# H04.net
KiCad netlist of a schematic drawn in EAGLE
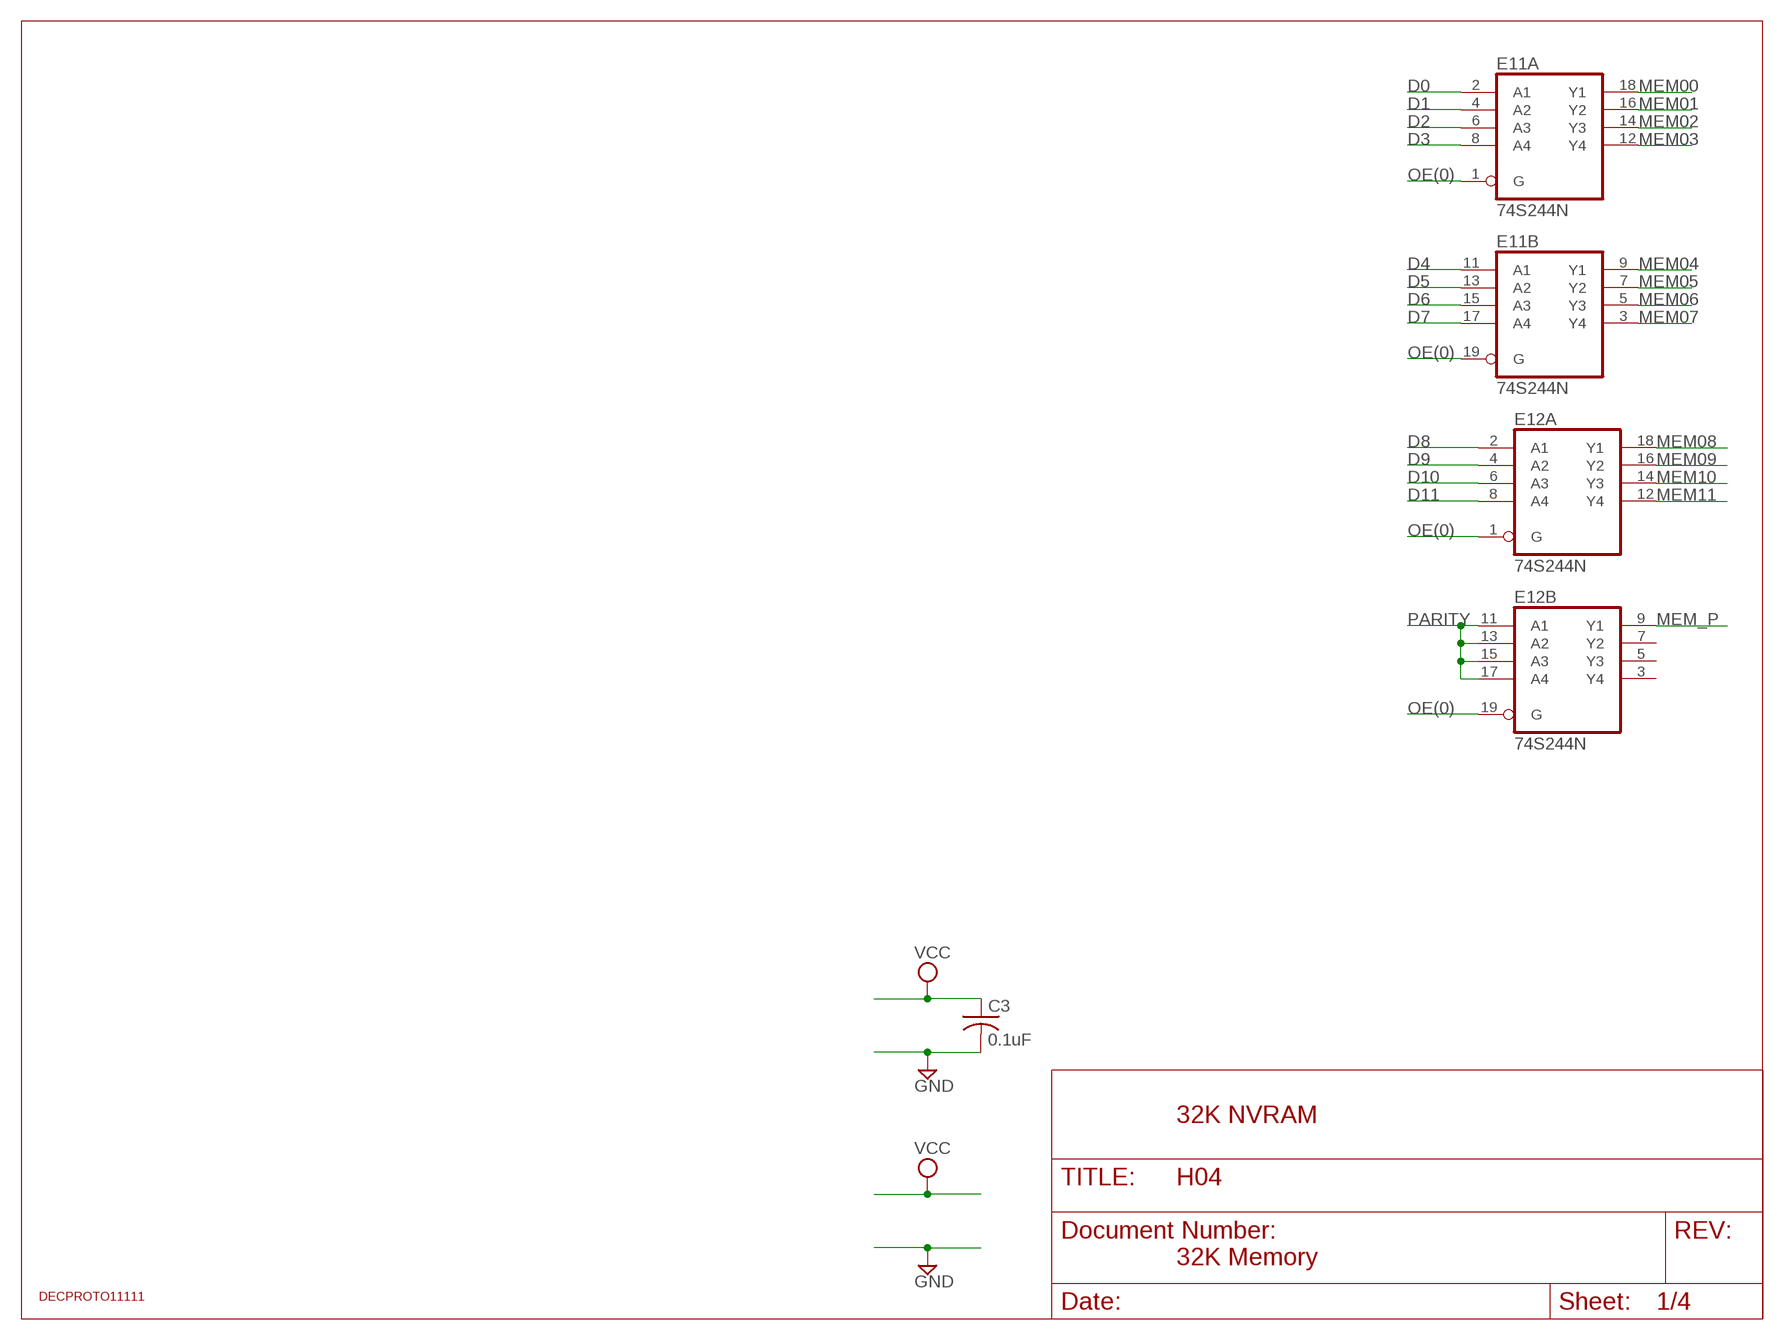
[diagram p0: schematic, sheet 1]
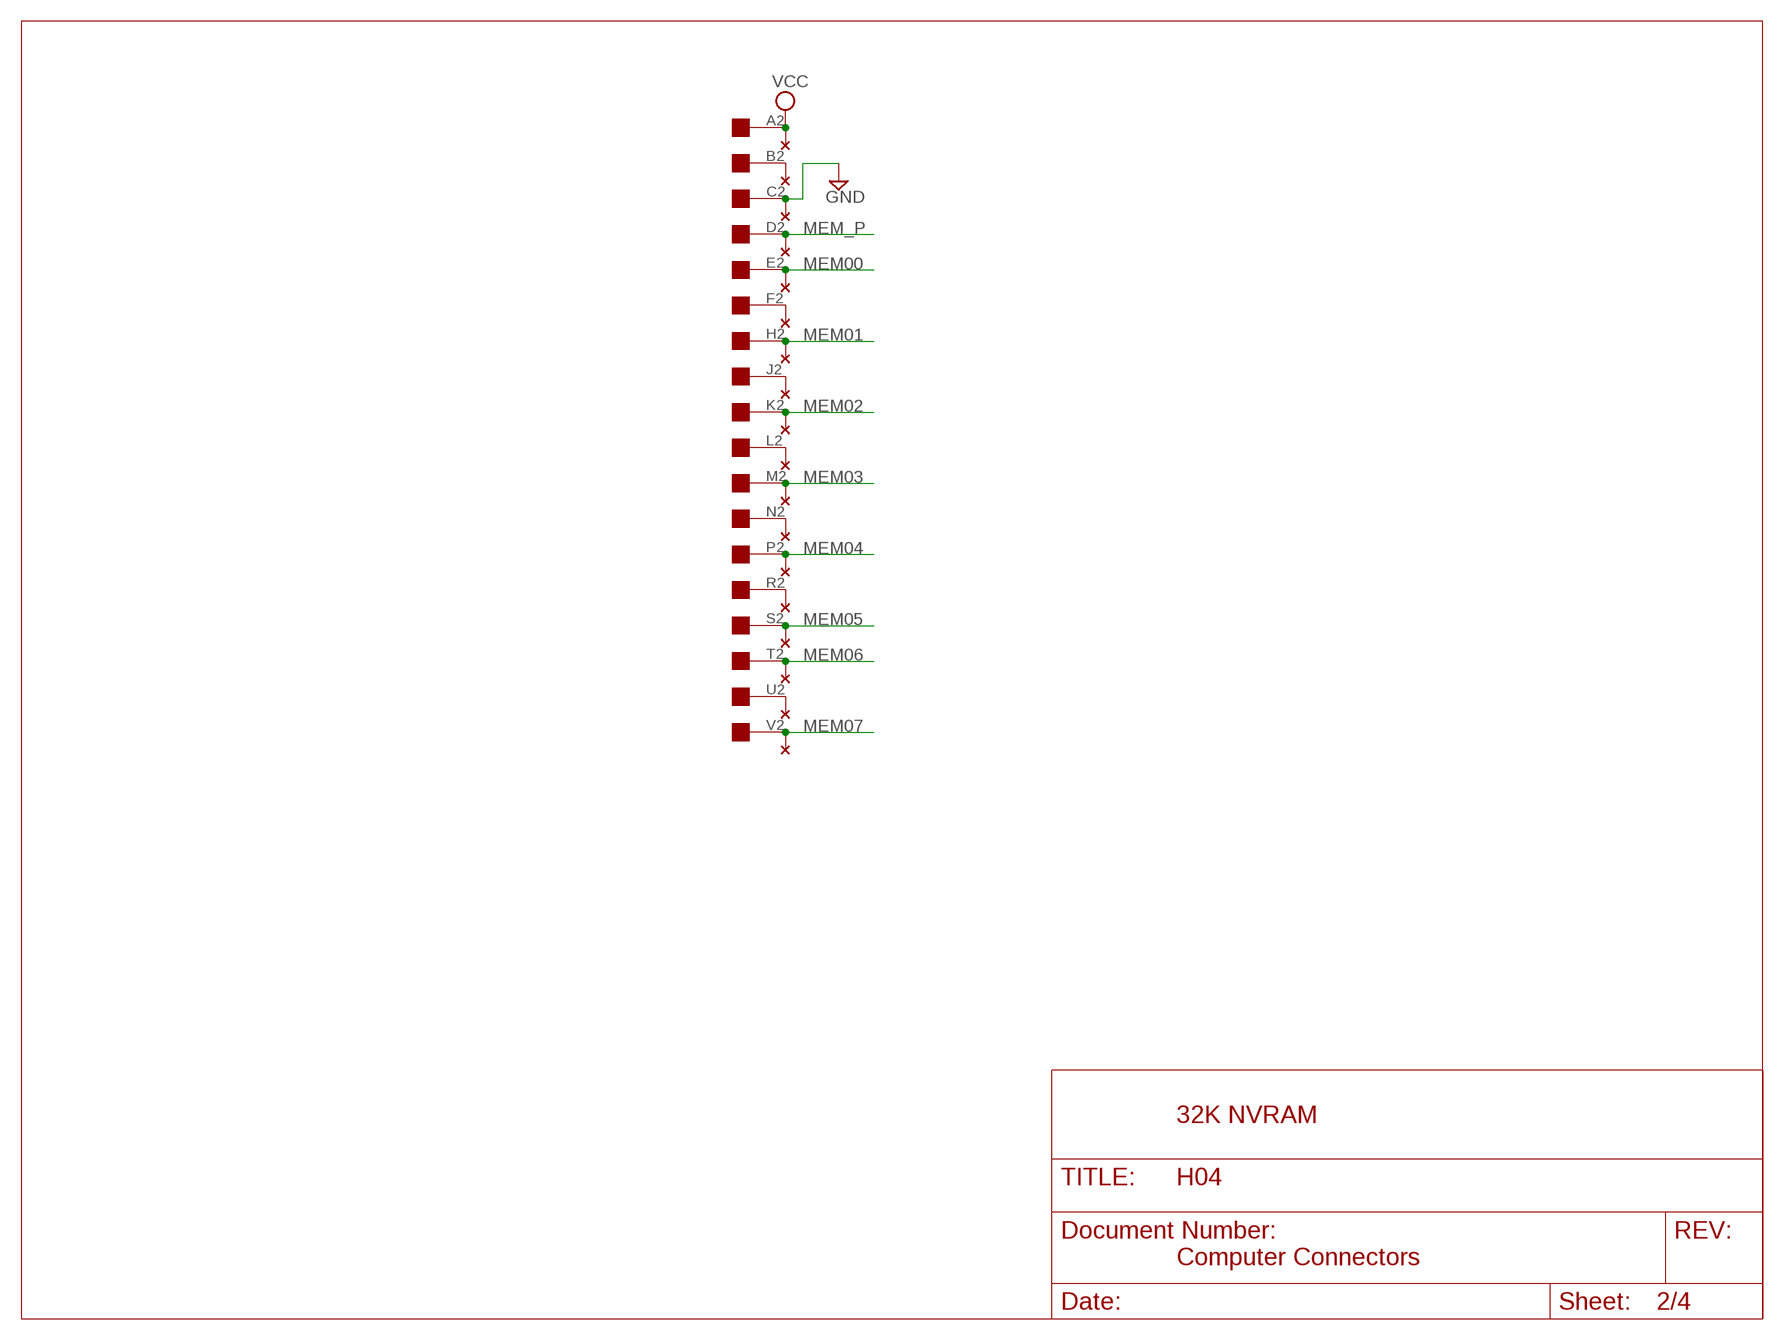
[diagram p1: schematic, sheet 2]
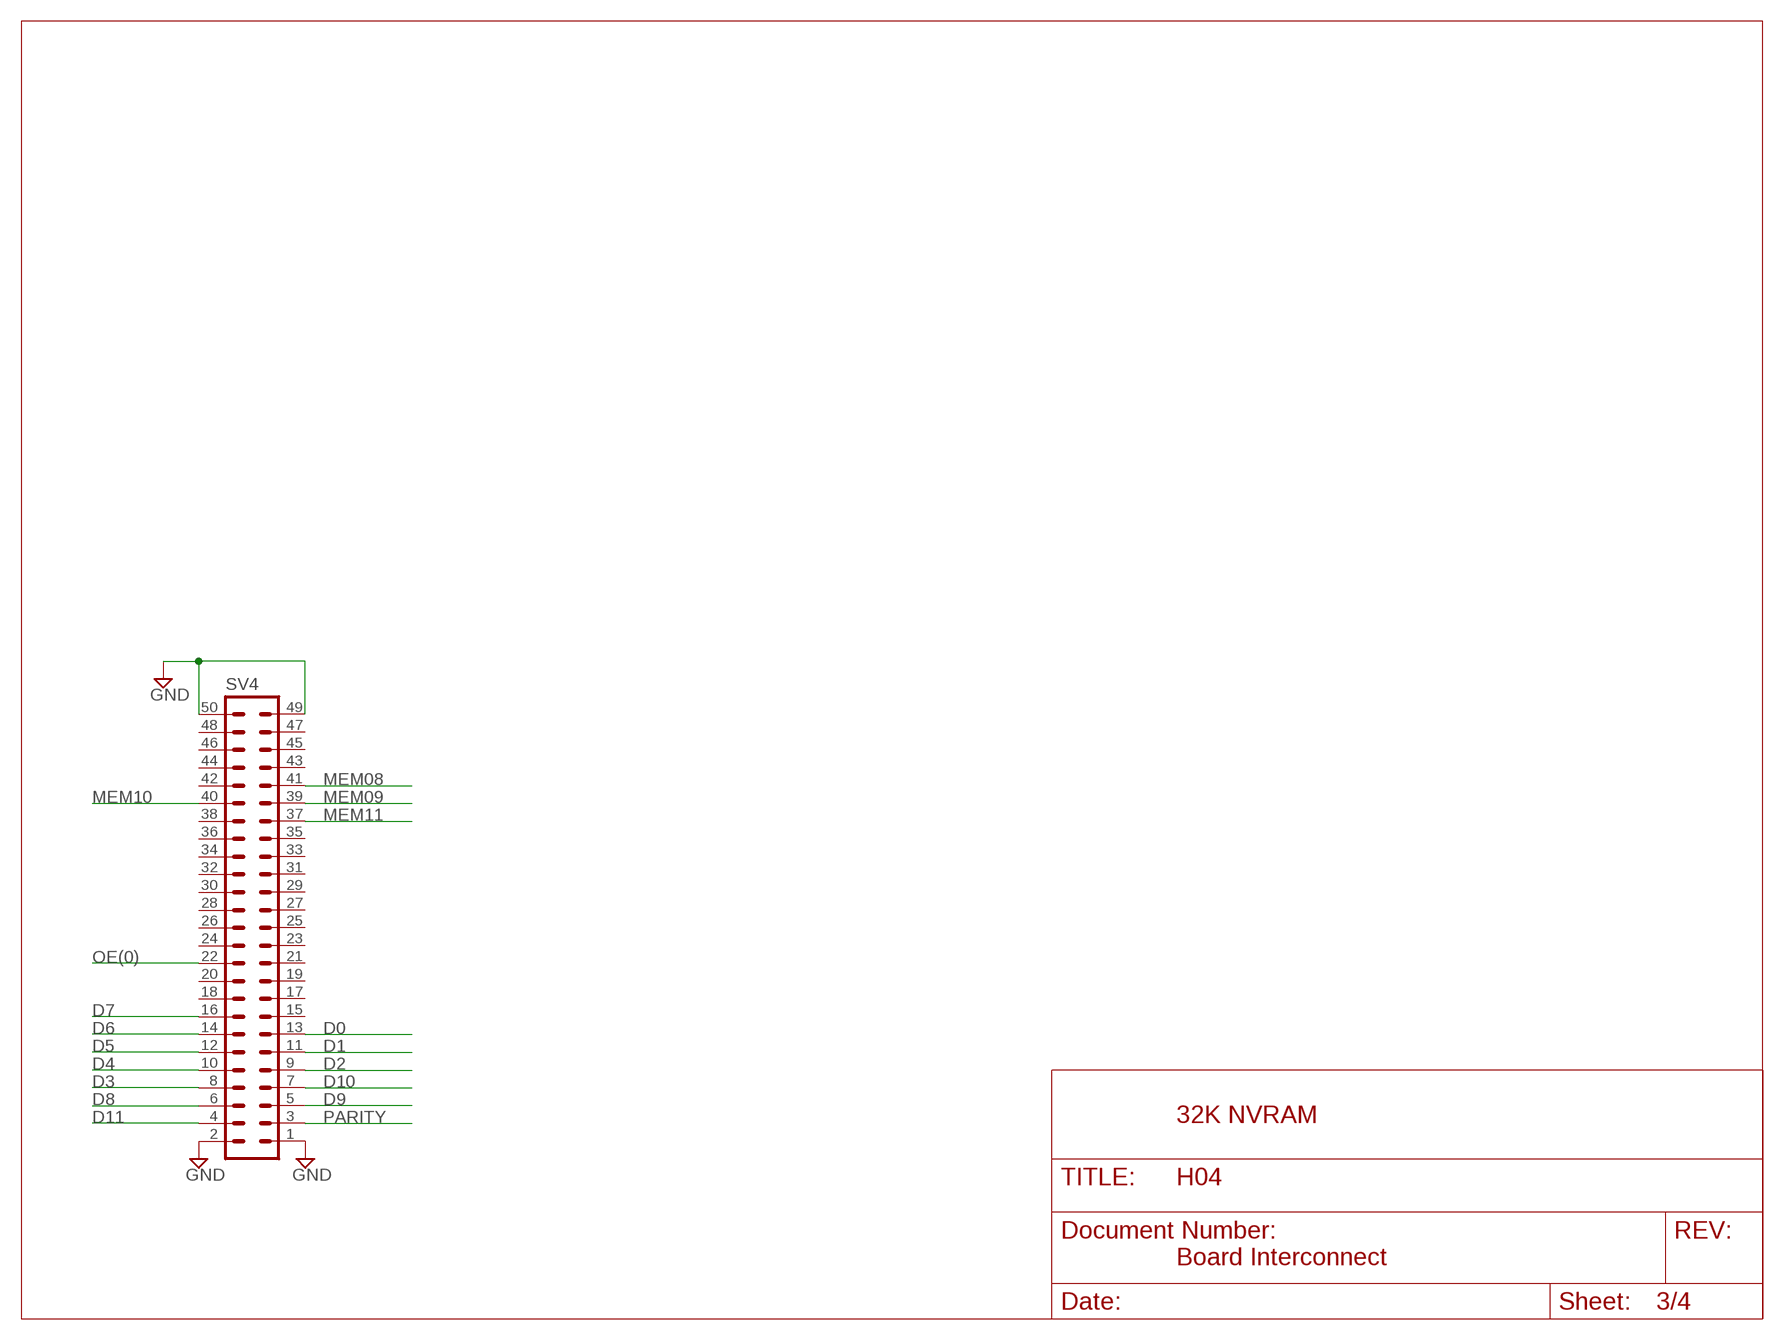
[diagram p2: schematic, sheet 3]
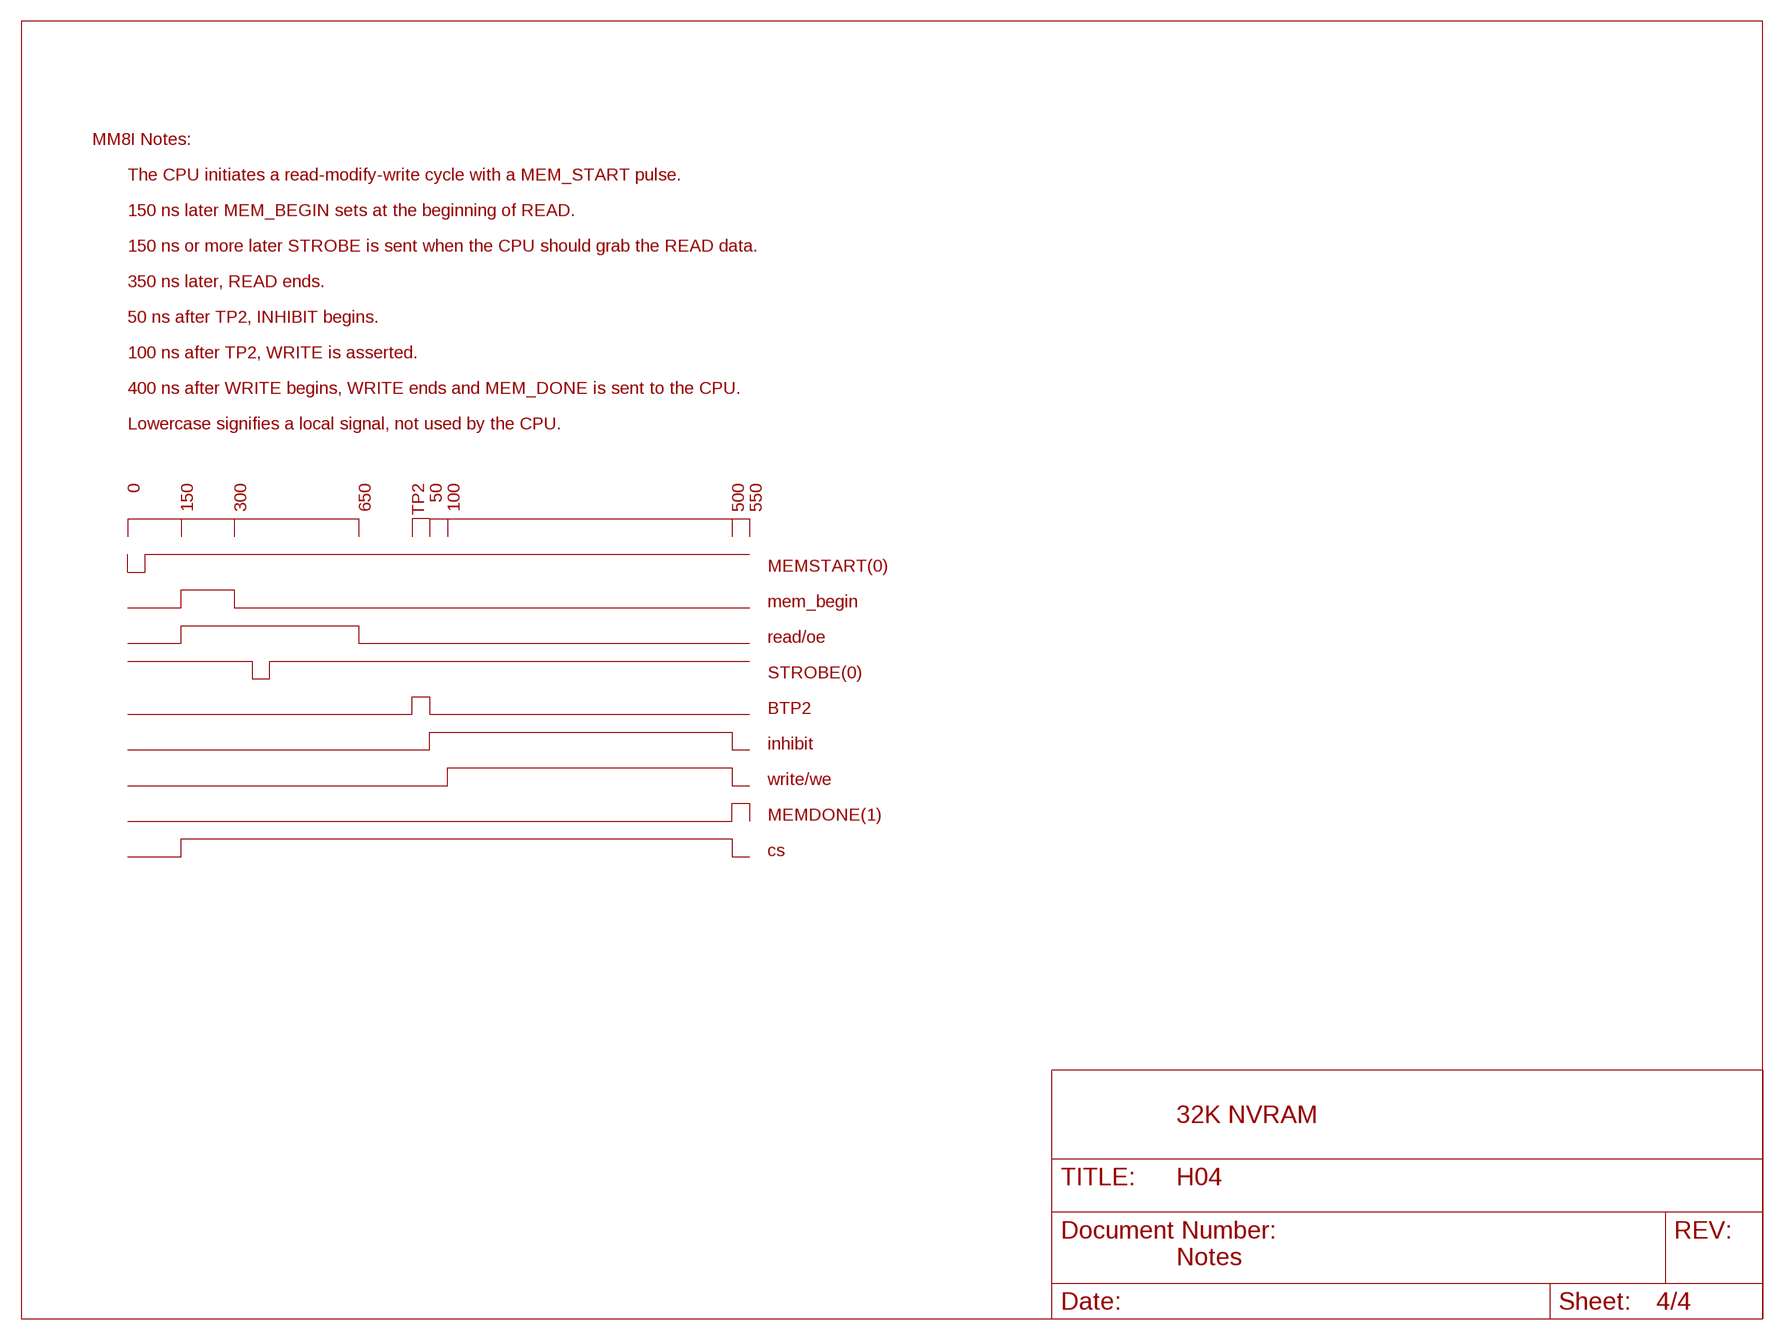
[diagram p3: schematic, sheet 4]

(export (version "E")
  (design (tool "Eeschema 10.0.6"))
  (components
    (comp (ref "SV4")
      (value "ML50L")
      (footprint "eagle-import:ML50L")
      (libsource (lib "eagle-import") (part "ML50L"))
    )
    (comp (ref "C3")
      (value "0.1uF")
      (footprint "eagle-import:C050-025X075")
      (libsource (lib "eagle-import") (part "C-US050-025X075"))
    )
    (comp (ref "E11")
      (value "74S244N")
      (footprint "eagle-import:DIL20")
      (libsource (lib "eagle-import") (part "74244NS"))
    )
    (comp (ref "E12")
      (value "74S244N")
      (footprint "eagle-import:DIL20")
      (libsource (lib "eagle-import") (part "74244NS"))
    )
    (comp (ref "U$6")
      (value "DECPROTO11111")
      (footprint "eagle-import:DECPROTO11111")
      (libsource (lib "eagle-import") (part "DECPROTO11111"))
    )
    (comp (ref "H04")
      (value "EDGE-1")
      (footprint "eagle-import:EDGE-CON1")
      (libsource (lib "eagle-import") (part "EDGE-1"))
    )
    (comp (ref "U$4")
      (value "THRU-HOLE2")
      (footprint "eagle-import:THRU-HOLEB")
      (libsource (lib "eagle-import") (part "THRU-HOLE2"))
    )
  )
  (nets
    (net (code "1") (name "D0") (class "Default")
      (node (ref "E11") (pin "2") (pinfunction "A1_2") (pintype "input"))
      (node (ref "SV4") (pin "13") (pinfunction "13_13") (pintype "passive"))
    )
    (net (code "2") (name "D1") (class "Default")
      (node (ref "E11") (pin "4") (pinfunction "A2_4") (pintype "input"))
      (node (ref "SV4") (pin "11") (pinfunction "11_11") (pintype "passive"))
    )
    (net (code "3") (name "D2") (class "Default")
      (node (ref "E11") (pin "6") (pinfunction "A3_6") (pintype "input"))
      (node (ref "SV4") (pin "9") (pinfunction "9_9") (pintype "passive"))
    )
    (net (code "4") (name "D3") (class "Default")
      (node (ref "E11") (pin "8") (pinfunction "A4_8") (pintype "input"))
      (node (ref "SV4") (pin "8") (pinfunction "8_8") (pintype "passive"))
    )
    (net (code "5") (name "D4") (class "Default")
      (node (ref "E11") (pin "11") (pinfunction "A1_11") (pintype "input"))
      (node (ref "SV4") (pin "10") (pinfunction "10_10") (pintype "passive"))
    )
    (net (code "6") (name "D5") (class "Default")
      (node (ref "E11") (pin "13") (pinfunction "A2_13") (pintype "input"))
      (node (ref "SV4") (pin "12") (pinfunction "12_12") (pintype "passive"))
    )
    (net (code "7") (name "D6") (class "Default")
      (node (ref "E11") (pin "15") (pinfunction "A3_15") (pintype "input"))
      (node (ref "SV4") (pin "14") (pinfunction "14_14") (pintype "passive"))
    )
    (net (code "8") (name "D7") (class "Default")
      (node (ref "E11") (pin "17") (pinfunction "A4_17") (pintype "input"))
      (node (ref "SV4") (pin "16") (pinfunction "16_16") (pintype "passive"))
    )
    (net (code "9") (name "D8") (class "Default")
      (node (ref "E12") (pin "2") (pinfunction "A1_2") (pintype "input"))
      (node (ref "SV4") (pin "6") (pinfunction "6_6") (pintype "passive"))
    )
    (net (code "10") (name "D9") (class "Default")
      (node (ref "E12") (pin "4") (pinfunction "A2_4") (pintype "input"))
      (node (ref "SV4") (pin "5") (pinfunction "5_5") (pintype "passive"))
    )
    (net (code "11") (name "D10") (class "Default")
      (node (ref "E12") (pin "6") (pinfunction "A3_6") (pintype "input"))
      (node (ref "SV4") (pin "7") (pinfunction "7_7") (pintype "passive"))
    )
    (net (code "12") (name "D11") (class "Default")
      (node (ref "E12") (pin "8") (pinfunction "A4_8") (pintype "input"))
      (node (ref "SV4") (pin "4") (pinfunction "4_4") (pintype "passive"))
    )
    (net (code "13") (name "GND") (class "Default")
      (node (ref "C3") (pin "2") (pinfunction "2_2") (pintype "passive"))
      (node (ref "H04") (pin "C2") (pinfunction "1_C2") (pintype "bidirectional"))
      (node (ref "SV4") (pin "1") (pinfunction "1_1") (pintype "passive"))
      (node (ref "SV4") (pin "2") (pinfunction "2_2") (pintype "passive"))
      (node (ref "SV4") (pin "49") (pinfunction "49_49") (pintype "passive"))
      (node (ref "SV4") (pin "50") (pinfunction "50_50") (pintype "passive"))
      (node (ref "U$4") (pin "C2") (pinfunction "P$1_C2") (pintype "passive"))
    )
    (net (code "14") (name "MEM00") (class "Default")
      (node (ref "E11") (pin "18") (pinfunction "Y1_18") (pintype "tri_state"))
      (node (ref "H04") (pin "E2") (pinfunction "1_E2") (pintype "bidirectional"))
      (node (ref "U$4") (pin "E2") (pinfunction "P$1_E2") (pintype "passive"))
    )
    (net (code "15") (name "MEM01") (class "Default")
      (node (ref "E11") (pin "16") (pinfunction "Y2_16") (pintype "tri_state"))
      (node (ref "H04") (pin "H2") (pinfunction "1_H2") (pintype "bidirectional"))
      (node (ref "U$4") (pin "H2") (pinfunction "P$1_H2") (pintype "passive"))
    )
    (net (code "16") (name "MEM02") (class "Default")
      (node (ref "E11") (pin "14") (pinfunction "Y3_14") (pintype "tri_state"))
      (node (ref "H04") (pin "K2") (pinfunction "1_K2") (pintype "bidirectional"))
      (node (ref "U$4") (pin "K2") (pinfunction "P$1_K2") (pintype "passive"))
    )
    (net (code "17") (name "MEM03") (class "Default")
      (node (ref "E11") (pin "12") (pinfunction "Y4_12") (pintype "tri_state"))
      (node (ref "H04") (pin "M2") (pinfunction "1_M2") (pintype "bidirectional"))
      (node (ref "U$4") (pin "M2") (pinfunction "P$1_M2") (pintype "passive"))
    )
    (net (code "18") (name "MEM04") (class "Default")
      (node (ref "E11") (pin "9") (pinfunction "Y1_9") (pintype "tri_state"))
      (node (ref "H04") (pin "P2") (pinfunction "1_P2") (pintype "bidirectional"))
      (node (ref "U$4") (pin "P2") (pinfunction "P$1_P2") (pintype "passive"))
    )
    (net (code "19") (name "MEM05") (class "Default")
      (node (ref "E11") (pin "7") (pinfunction "Y2_7") (pintype "tri_state"))
      (node (ref "H04") (pin "S2") (pinfunction "1_S2") (pintype "bidirectional"))
      (node (ref "U$4") (pin "S2") (pinfunction "P$1_S2") (pintype "passive"))
    )
    (net (code "20") (name "MEM06") (class "Default")
      (node (ref "E11") (pin "5") (pinfunction "Y3_5") (pintype "tri_state"))
      (node (ref "H04") (pin "T2") (pinfunction "1_T2") (pintype "bidirectional"))
      (node (ref "U$4") (pin "T2") (pinfunction "P$1_T2") (pintype "passive"))
    )
    (net (code "21") (name "MEM07") (class "Default")
      (node (ref "E11") (pin "3") (pinfunction "Y4_3") (pintype "tri_state"))
      (node (ref "H04") (pin "V2") (pinfunction "1_V2") (pintype "bidirectional"))
      (node (ref "U$4") (pin "V2") (pinfunction "P$1_V2") (pintype "passive"))
    )
    (net (code "22") (name "MEM08") (class "Default")
      (node (ref "E12") (pin "18") (pinfunction "Y1_18") (pintype "tri_state"))
      (node (ref "SV4") (pin "41") (pinfunction "41_41") (pintype "passive"))
    )
    (net (code "23") (name "MEM09") (class "Default")
      (node (ref "E12") (pin "16") (pinfunction "Y2_16") (pintype "tri_state"))
      (node (ref "SV4") (pin "39") (pinfunction "39_39") (pintype "passive"))
    )
    (net (code "24") (name "MEM10") (class "Default")
      (node (ref "E12") (pin "14") (pinfunction "Y3_14") (pintype "tri_state"))
      (node (ref "SV4") (pin "40") (pinfunction "40_40") (pintype "passive"))
    )
    (net (code "25") (name "MEM11") (class "Default")
      (node (ref "E12") (pin "12") (pinfunction "Y4_12") (pintype "tri_state"))
      (node (ref "SV4") (pin "37") (pinfunction "37_37") (pintype "passive"))
    )
    (net (code "26") (name "MEM_P") (class "Default")
      (node (ref "E12") (pin "9") (pinfunction "Y1_9") (pintype "tri_state"))
      (node (ref "H04") (pin "D2") (pinfunction "1_D2") (pintype "bidirectional"))
      (node (ref "U$4") (pin "D2") (pinfunction "P$1_D2") (pintype "passive"))
    )
    (net (code "27") (name "Net-(H04B-1)") (class "Default")
      (node (ref "H04") (pin "B2") (pinfunction "1_B2") (pintype "bidirectional"))
      (node (ref "U$4") (pin "B2") (pinfunction "P$1_B2") (pintype "passive"))
    )
    (net (code "28") (name "Net-(H04F-1)") (class "Default")
      (node (ref "H04") (pin "F2") (pinfunction "1_F2") (pintype "bidirectional"))
      (node (ref "U$4") (pin "F2") (pinfunction "P$1_F2") (pintype "passive"))
    )
    (net (code "29") (name "Net-(H04H-1)") (class "Default")
      (node (ref "H04") (pin "J2") (pinfunction "1_J2") (pintype "bidirectional"))
      (node (ref "U$4") (pin "J2") (pinfunction "P$1_J2") (pintype "passive"))
    )
    (net (code "30") (name "Net-(H04J-1)") (class "Default")
      (node (ref "H04") (pin "L2") (pinfunction "1_L2") (pintype "bidirectional"))
      (node (ref "U$4") (pin "L2") (pinfunction "P$1_L2") (pintype "passive"))
    )
    (net (code "31") (name "Net-(H04L-1)") (class "Default")
      (node (ref "H04") (pin "N2") (pinfunction "1_N2") (pintype "bidirectional"))
      (node (ref "U$4") (pin "N2") (pinfunction "P$1_N2") (pintype "passive"))
    )
    (net (code "32") (name "Net-(H04N-1)") (class "Default")
      (node (ref "H04") (pin "R2") (pinfunction "1_R2") (pintype "bidirectional"))
      (node (ref "U$4") (pin "R2") (pinfunction "P$1_R2") (pintype "passive"))
    )
    (net (code "33") (name "Net-(H04Q-1)") (class "Default")
      (node (ref "H04") (pin "U2") (pinfunction "1_U2") (pintype "bidirectional"))
      (node (ref "U$4") (pin "U2") (pinfunction "P$1_U2") (pintype "passive"))
    )
    (net (code "34") (name "OE(0)") (class "Default")
      (node (ref "E11") (pin "1") (pinfunction "G_1") (pintype "input"))
      (node (ref "E11") (pin "19") (pinfunction "G_19") (pintype "input"))
      (node (ref "E12") (pin "1") (pinfunction "G_1") (pintype "input"))
      (node (ref "E12") (pin "19") (pinfunction "G_19") (pintype "input"))
      (node (ref "SV4") (pin "22") (pinfunction "22_22") (pintype "passive"))
    )
    (net (code "35") (name "PARITY") (class "Default")
      (node (ref "E12") (pin "11") (pinfunction "A1_11") (pintype "input"))
      (node (ref "E12") (pin "13") (pinfunction "A2_13") (pintype "input"))
      (node (ref "E12") (pin "15") (pinfunction "A3_15") (pintype "input"))
      (node (ref "E12") (pin "17") (pinfunction "A4_17") (pintype "input"))
      (node (ref "SV4") (pin "3") (pinfunction "3_3") (pintype "passive"))
    )
    (net (code "36") (name "VCC") (class "Default")
      (node (ref "C3") (pin "1") (pinfunction "1_1") (pintype "passive"))
      (node (ref "H04") (pin "A2") (pinfunction "1_A2") (pintype "bidirectional"))
      (node (ref "U$4") (pin "A2") (pinfunction "P$1_A2") (pintype "passive"))
    )
    (net (code "37") (name "unconnected-(E12B-Y2-Pad7)") (class "Default")
      (node (ref "E12") (pin "7") (pinfunction "Y2_7") (pintype "tri_state"))
    )
    (net (code "38") (name "unconnected-(E12B-Y3-Pad5)") (class "Default")
      (node (ref "E12") (pin "5") (pinfunction "Y3_5") (pintype "tri_state"))
    )
    (net (code "39") (name "unconnected-(E12B-Y4-Pad3)") (class "Default")
      (node (ref "E12") (pin "3") (pinfunction "Y4_3") (pintype "tri_state"))
    )
    (net (code "40") (name "unconnected-(SV4-Pad15)") (class "Default")
      (node (ref "SV4") (pin "15") (pinfunction "15_15") (pintype "passive"))
    )
    (net (code "41") (name "unconnected-(SV4-Pad17)") (class "Default")
      (node (ref "SV4") (pin "17") (pinfunction "17_17") (pintype "passive"))
    )
    (net (code "42") (name "unconnected-(SV4-Pad18)") (class "Default")
      (node (ref "SV4") (pin "18") (pinfunction "18_18") (pintype "passive"))
    )
    (net (code "43") (name "unconnected-(SV4-Pad19)") (class "Default")
      (node (ref "SV4") (pin "19") (pinfunction "19_19") (pintype "passive"))
    )
    (net (code "44") (name "unconnected-(SV4-Pad20)") (class "Default")
      (node (ref "SV4") (pin "20") (pinfunction "20_20") (pintype "passive"))
    )
    (net (code "45") (name "unconnected-(SV4-Pad21)") (class "Default")
      (node (ref "SV4") (pin "21") (pinfunction "21_21") (pintype "passive"))
    )
    (net (code "46") (name "unconnected-(SV4-Pad23)") (class "Default")
      (node (ref "SV4") (pin "23") (pinfunction "23_23") (pintype "passive"))
    )
    (net (code "47") (name "unconnected-(SV4-Pad24)") (class "Default")
      (node (ref "SV4") (pin "24") (pinfunction "24_24") (pintype "passive"))
    )
    (net (code "48") (name "unconnected-(SV4-Pad25)") (class "Default")
      (node (ref "SV4") (pin "25") (pinfunction "25_25") (pintype "passive"))
    )
    (net (code "49") (name "unconnected-(SV4-Pad26)") (class "Default")
      (node (ref "SV4") (pin "26") (pinfunction "26_26") (pintype "passive"))
    )
    (net (code "50") (name "unconnected-(SV4-Pad27)") (class "Default")
      (node (ref "SV4") (pin "27") (pinfunction "27_27") (pintype "passive"))
    )
    (net (code "51") (name "unconnected-(SV4-Pad28)") (class "Default")
      (node (ref "SV4") (pin "28") (pinfunction "28_28") (pintype "passive"))
    )
    (net (code "52") (name "unconnected-(SV4-Pad29)") (class "Default")
      (node (ref "SV4") (pin "29") (pinfunction "29_29") (pintype "passive"))
    )
    (net (code "53") (name "unconnected-(SV4-Pad30)") (class "Default")
      (node (ref "SV4") (pin "30") (pinfunction "30_30") (pintype "passive"))
    )
    (net (code "54") (name "unconnected-(SV4-Pad31)") (class "Default")
      (node (ref "SV4") (pin "31") (pinfunction "31_31") (pintype "passive"))
    )
    (net (code "55") (name "unconnected-(SV4-Pad32)") (class "Default")
      (node (ref "SV4") (pin "32") (pinfunction "32_32") (pintype "passive"))
    )
    (net (code "56") (name "unconnected-(SV4-Pad33)") (class "Default")
      (node (ref "SV4") (pin "33") (pinfunction "33_33") (pintype "passive"))
    )
    (net (code "57") (name "unconnected-(SV4-Pad34)") (class "Default")
      (node (ref "SV4") (pin "34") (pinfunction "34_34") (pintype "passive"))
    )
    (net (code "58") (name "unconnected-(SV4-Pad35)") (class "Default")
      (node (ref "SV4") (pin "35") (pinfunction "35_35") (pintype "passive"))
    )
    (net (code "59") (name "unconnected-(SV4-Pad36)") (class "Default")
      (node (ref "SV4") (pin "36") (pinfunction "36_36") (pintype "passive"))
    )
    (net (code "60") (name "unconnected-(SV4-Pad38)") (class "Default")
      (node (ref "SV4") (pin "38") (pinfunction "38_38") (pintype "passive"))
    )
    (net (code "61") (name "unconnected-(SV4-Pad42)") (class "Default")
      (node (ref "SV4") (pin "42") (pinfunction "42_42") (pintype "passive"))
    )
    (net (code "62") (name "unconnected-(SV4-Pad43)") (class "Default")
      (node (ref "SV4") (pin "43") (pinfunction "43_43") (pintype "passive"))
    )
    (net (code "63") (name "unconnected-(SV4-Pad44)") (class "Default")
      (node (ref "SV4") (pin "44") (pinfunction "44_44") (pintype "passive"))
    )
    (net (code "64") (name "unconnected-(SV4-Pad45)") (class "Default")
      (node (ref "SV4") (pin "45") (pinfunction "45_45") (pintype "passive"))
    )
    (net (code "65") (name "unconnected-(SV4-Pad46)") (class "Default")
      (node (ref "SV4") (pin "46") (pinfunction "46_46") (pintype "passive"))
    )
    (net (code "66") (name "unconnected-(SV4-Pad47)") (class "Default")
      (node (ref "SV4") (pin "47") (pinfunction "47_47") (pintype "passive"))
    )
    (net (code "67") (name "unconnected-(SV4-Pad48)") (class "Default")
      (node (ref "SV4") (pin "48") (pinfunction "48_48") (pintype "passive"))
    )
  )
)
